# Logic-Board.net
KiCad netlist of a schematic drawn in EAGLE
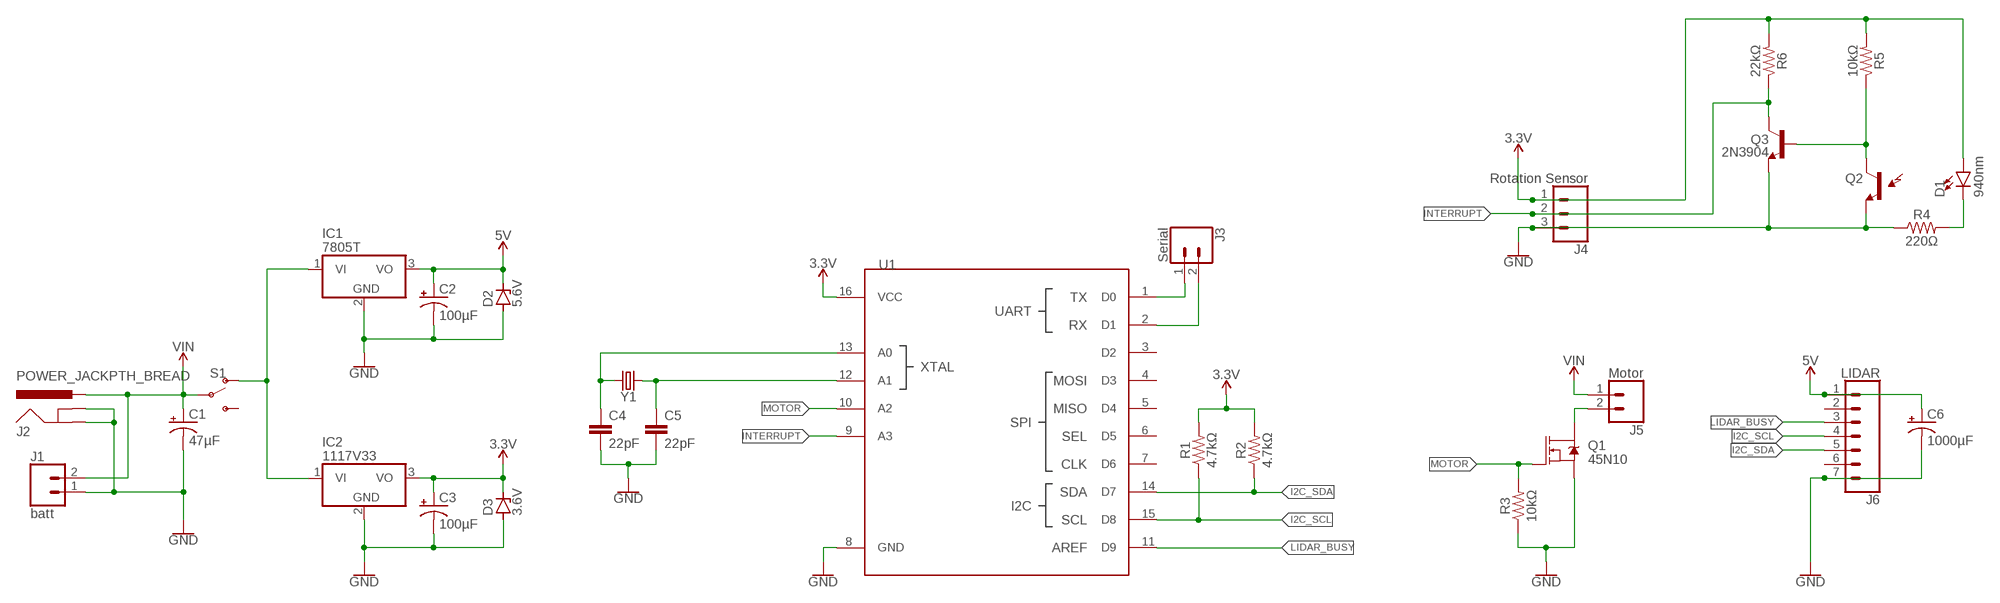
[diagram p0: schematic, sheet 1]

(export (version "E")
  (design (tool "Eeschema 10.0.6"))
  (components
    (comp (ref "C1")
      (value "47µF")
      (footprint "eagle-import:E3,5-10")
      (libsource (lib "eagle-import") (part "CPOL-USE3.5-10"))
    )
    (comp (ref "C2")
      (value "100µF")
      (footprint "eagle-import:E3,5-10")
      (libsource (lib "eagle-import") (part "CPOL-USE3.5-10"))
    )
    (comp (ref "C3")
      (value "100µF")
      (footprint "eagle-import:E3,5-10")
      (libsource (lib "eagle-import") (part "CPOL-USE3.5-10"))
    )
    (comp (ref "C4")
      (value "22pF")
      (footprint "eagle-import:C2.5-3")
      (libsource (lib "eagle-import") (part "C2,5-3"))
    )
    (comp (ref "C5")
      (value "22pF")
      (footprint "eagle-import:C2.5-3")
      (libsource (lib "eagle-import") (part "C2,5-3"))
    )
    (comp (ref "C6")
      (value "1000µF")
      (footprint "eagle-import:E3,5-10")
      (libsource (lib "eagle-import") (part "CPOL-USE3.5-10"))
    )
    (comp (ref "D1")
      (value "940nm")
      (footprint "eagle-import:LED_3MM-NS")
      (libsource (lib "eagle-import") (part "LED-3MM-NO_SILK"))
    )
    (comp (ref "D2")
      (value "5.6V")
      (footprint "eagle-import:DO41Z10")
      (libsource (lib "eagle-import") (part "ZENER-DIODEDO41Z10"))
    )
    (comp (ref "D3")
      (value "3.6V")
      (footprint "eagle-import:DO41Z10")
      (libsource (lib "eagle-import") (part "ZENER-DIODEDO41Z10"))
    )
    (comp (ref "IC1")
      (value "7805T")
      (footprint "eagle-import:TO220H")
      (libsource (lib "eagle-import") (part "78T05"))
    )
    (comp (ref "IC2")
      (value "1117V33")
      (footprint "eagle-import:TO220H")
      (libsource (lib "eagle-import") (part "78T05"))
    )
    (comp (ref "J1")
      (value "batt")
      (footprint "eagle-import:MOLEX-1X2_LOCK")
      (libsource (lib "eagle-import") (part "CONN_02POLAR_LOCK"))
    )
    (comp (ref "J2")
      (value "POWER_JACKPTH_BREAD")
      (footprint "eagle-import:POWER_JACK_PTH_BREAD")
      (libsource (lib "eagle-import") (part "POWER_JACKPTH_BREAD"))
    )
    (comp (ref "J3")
      (value "Serial")
      (footprint "eagle-import:MOLEX-1X2_LOCK")
      (libsource (lib "eagle-import") (part "CONN_02POLAR_LOCK"))
    )
    (comp (ref "J4")
      (value "Rotation Sensor")
      (footprint "eagle-import:MOLEX-1X3")
      (libsource (lib "eagle-import") (part "CONN_03POLAR"))
    )
    (comp (ref "J5")
      (value "Motor")
      (footprint "eagle-import:MOLEX-1X2_LOCK")
      (libsource (lib "eagle-import") (part "CONN_02POLAR_LOCK"))
    )
    (comp (ref "J6")
      (value "LIDAR")
      (footprint "eagle-import:1X07")
      (libsource (lib "eagle-import") (part "CONN_07"))
    )
    (comp (ref "Q1")
      (value "45N10")
      (footprint "eagle-import:TO220V")
      (libsource (lib "eagle-import") (part "MOSFET-NCH-FQP30N06L"))
    )
    (comp (ref "Q2")
      (value "LTR-301")
      (footprint "eagle-import:LTR-301")
      (libsource (lib "eagle-import") (part "LTR-301"))
    )
    (comp (ref "Q3")
      (value "2N3904")
      (footprint "eagle-import:TO-92")
      (libsource (lib "eagle-import") (part "TRANS_NPN-2N3904"))
    )
    (comp (ref "R1")
      (value "4.7kΩ")
      (footprint "eagle-import:AXIAL-0.3-KIT")
      (libsource (lib "eagle-import") (part "1KOHM-HORIZ_KIT-1/4W-1%"))
    )
    (comp (ref "R2")
      (value "4.7kΩ")
      (footprint "eagle-import:AXIAL-0.3-KIT")
      (libsource (lib "eagle-import") (part "1KOHM-HORIZ_KIT-1/4W-1%"))
    )
    (comp (ref "R3")
      (value "10kΩ")
      (footprint "eagle-import:AXIAL-0.3-KIT")
      (libsource (lib "eagle-import") (part "1KOHM-HORIZ_KIT-1/4W-1%"))
    )
    (comp (ref "R4")
      (value "220Ω")
      (footprint "eagle-import:AXIAL-0.3-KIT")
      (libsource (lib "eagle-import") (part "1KOHM-HORIZ_KIT-1/4W-1%"))
    )
    (comp (ref "R5")
      (value "10kΩ")
      (footprint "eagle-import:AXIAL-0.3-KIT")
      (libsource (lib "eagle-import") (part "1KOHM-HORIZ_KIT-1/4W-1%"))
    )
    (comp (ref "R6")
      (value "22kΩ")
      (footprint "eagle-import:AXIAL-0.3-KIT")
      (libsource (lib "eagle-import") (part "1KOHM-HORIZ_KIT-1/4W-1%"))
    )
    (comp (ref "S1")
      (value "SWITCH-SPDT-PTH-11.6X4.0MM")
      (footprint "eagle-import:SWITCH_SPDT_PTH_11.6X4.0MM")
      (libsource (lib "eagle-import") (part "SWITCH-SPDT-PTH-11.6X4.0MM"))
    )
    (comp (ref "U1")
      (value "OSHCHIP")
      (footprint "eagle-import:SOCKET-16")
      (libsource (lib "eagle-import") (part "OSHCHIP"))
    )
    (comp (ref "Y1")
      (value "CRYSTALPTH-3X8")
      (footprint "eagle-import:CRYSTAL-PTH-3X8-CYL")
      (libsource (lib "eagle-import") (part "CRYSTALPTH-3X8"))
    )
  )
  (nets
    (net (code "1") (name "3.3V") (class "Default")
      (node (ref "C3") (pin "+") (pinfunction "+_+") (pintype "passive"))
      (node (ref "D1") (pin "A") (pinfunction "A_A") (pintype "passive"))
      (node (ref "D3") (pin "C") (pinfunction "C_C") (pintype "passive"))
      (node (ref "IC2") (pin "3") (pinfunction "VO_3") (pintype "passive"))
      (node (ref "J4") (pin "1") (pinfunction "1_1") (pintype "passive"))
      (node (ref "R1") (pin "P$2") (pinfunction "2_P$2") (pintype "passive"))
      (node (ref "R2") (pin "P$2") (pinfunction "2_P$2") (pintype "passive"))
      (node (ref "R5") (pin "P$2") (pinfunction "2_P$2") (pintype "passive"))
      (node (ref "R6") (pin "P$2") (pinfunction "2_P$2") (pintype "passive"))
      (node (ref "U1") (pin "16") (pinfunction "VCC_16") (pintype "bidirectional"))
    )
    (net (code "2") (name "5V") (class "Default")
      (node (ref "C2") (pin "+") (pinfunction "+_+") (pintype "passive"))
      (node (ref "C6") (pin "+") (pinfunction "+_+") (pintype "passive"))
      (node (ref "D2") (pin "C") (pinfunction "C_C") (pintype "passive"))
      (node (ref "IC1") (pin "3") (pinfunction "VO_3") (pintype "passive"))
      (node (ref "J6") (pin "1") (pinfunction "1_1") (pintype "passive"))
    )
    (net (code "3") (name "GND") (class "Default")
      (node (ref "C1") (pin "-") (pinfunction "-_-") (pintype "passive"))
      (node (ref "C2") (pin "-") (pinfunction "-_-") (pintype "passive"))
      (node (ref "C3") (pin "-") (pinfunction "-_-") (pintype "passive"))
      (node (ref "C4") (pin "2") (pinfunction "2_2") (pintype "passive"))
      (node (ref "C5") (pin "2") (pinfunction "2_2") (pintype "passive"))
      (node (ref "C6") (pin "-") (pinfunction "-_-") (pintype "passive"))
      (node (ref "D2") (pin "A") (pinfunction "A_A") (pintype "passive"))
      (node (ref "D3") (pin "A") (pinfunction "A_A") (pintype "passive"))
      (node (ref "IC1") (pin "2") (pinfunction "GND_2") (pintype "passive"))
      (node (ref "IC2") (pin "2") (pinfunction "GND_2") (pintype "passive"))
      (node (ref "J1") (pin "1") (pinfunction "1_1") (pintype "passive"))
      (node (ref "J2") (pin "GND") (pinfunction "GND_GND") (pintype "bidirectional"))
      (node (ref "J2") (pin "GNDBREAK") (pinfunction "GNDBREAK_GNDBREAK") (pintype "bidirectional"))
      (node (ref "J4") (pin "3") (pinfunction "3_3") (pintype "passive"))
      (node (ref "J6") (pin "7") (pinfunction "7_7") (pintype "passive"))
      (node (ref "Q1") (pin "3") (pinfunction "S_3") (pintype "bidirectional"))
      (node (ref "Q2") (pin "E") (pinfunction "E1_E") (pintype "passive"))
      (node (ref "Q3") (pin "1") (pinfunction "E_1") (pintype "passive"))
      (node (ref "R3") (pin "P$1") (pinfunction "1_P$1") (pintype "passive"))
      (node (ref "R4") (pin "P$1") (pinfunction "1_P$1") (pintype "passive"))
      (node (ref "U1") (pin "8") (pinfunction "GND_8") (pintype "bidirectional"))
    )
    (net (code "4") (name "I2C_SCL") (class "Default")
      (node (ref "J6") (pin "4") (pinfunction "4_4") (pintype "passive"))
      (node (ref "R1") (pin "P$1") (pinfunction "1_P$1") (pintype "passive"))
      (node (ref "U1") (pin "15") (pinfunction "D8_15") (pintype "bidirectional"))
    )
    (net (code "5") (name "I2C_SDA") (class "Default")
      (node (ref "J6") (pin "5") (pinfunction "5_5") (pintype "passive"))
      (node (ref "R2") (pin "P$1") (pinfunction "1_P$1") (pintype "passive"))
      (node (ref "U1") (pin "14") (pinfunction "D7_14") (pintype "bidirectional"))
    )
    (net (code "6") (name "INTERRUPT") (class "Default")
      (node (ref "J4") (pin "2") (pinfunction "2_2") (pintype "passive"))
      (node (ref "Q3") (pin "3") (pinfunction "C_3") (pintype "passive"))
      (node (ref "R6") (pin "P$1") (pinfunction "1_P$1") (pintype "passive"))
      (node (ref "U1") (pin "9") (pinfunction "A3_9") (pintype "bidirectional"))
    )
    (net (code "7") (name "LIDAR_BUSY") (class "Default")
      (node (ref "J6") (pin "3") (pinfunction "3_3") (pintype "passive"))
      (node (ref "U1") (pin "11") (pinfunction "D9_11") (pintype "bidirectional"))
    )
    (net (code "8") (name "MOTOR") (class "Default")
      (node (ref "Q1") (pin "1") (pinfunction "G_1") (pintype "bidirectional"))
      (node (ref "R3") (pin "P$2") (pinfunction "2_P$2") (pintype "passive"))
      (node (ref "U1") (pin "10") (pinfunction "A2_10") (pintype "bidirectional"))
    )
    (net (code "9") (name "Net-(D1-C)") (class "Default")
      (node (ref "D1") (pin "K") (pinfunction "C_K") (pintype "passive"))
      (node (ref "R4") (pin "P$2") (pinfunction "2_P$2") (pintype "passive"))
    )
    (net (code "10") (name "Net-(IC1-VI)") (class "Default")
      (node (ref "IC1") (pin "1") (pinfunction "VI_1") (pintype "input"))
      (node (ref "IC2") (pin "1") (pinfunction "VI_1") (pintype "input"))
      (node (ref "S1") (pin "1") (pinfunction "O_1") (pintype "passive"))
    )
    (net (code "11") (name "Net-(Q1-D)") (class "Default")
      (node (ref "J5") (pin "2") (pinfunction "2_2") (pintype "passive"))
      (node (ref "Q1") (pin "2") (pinfunction "D_2") (pintype "bidirectional"))
    )
    (net (code "12") (name "Net-(Q2-C1)") (class "Default")
      (node (ref "Q2") (pin "C") (pinfunction "C1_C") (pintype "passive"))
      (node (ref "Q3") (pin "2") (pinfunction "B_2") (pintype "passive"))
      (node (ref "R5") (pin "P$1") (pinfunction "1_P$1") (pintype "passive"))
    )
    (net (code "13") (name "Net-(U1-A0)") (class "Default")
      (node (ref "C4") (pin "1") (pinfunction "1_1") (pintype "passive"))
      (node (ref "U1") (pin "13") (pinfunction "A0_13") (pintype "bidirectional"))
      (node (ref "Y1") (pin "2") (pinfunction "2_2") (pintype "passive"))
    )
    (net (code "14") (name "Net-(U1-A1)") (class "Default")
      (node (ref "C5") (pin "1") (pinfunction "1_1") (pintype "passive"))
      (node (ref "U1") (pin "12") (pinfunction "A1_12") (pintype "bidirectional"))
      (node (ref "Y1") (pin "1") (pinfunction "1_1") (pintype "passive"))
    )
    (net (code "15") (name "Net-(U1-D0)") (class "Default")
      (node (ref "J3") (pin "1") (pinfunction "1_1") (pintype "passive"))
      (node (ref "U1") (pin "1") (pinfunction "D0_1") (pintype "bidirectional"))
    )
    (net (code "16") (name "Net-(U1-D1)") (class "Default")
      (node (ref "J3") (pin "2") (pinfunction "2_2") (pintype "passive"))
      (node (ref "U1") (pin "2") (pinfunction "D1_2") (pintype "bidirectional"))
    )
    (net (code "17") (name "VIN") (class "Default")
      (node (ref "C1") (pin "+") (pinfunction "+_+") (pintype "passive"))
      (node (ref "J1") (pin "2") (pinfunction "2_2") (pintype "passive"))
      (node (ref "J2") (pin "PWR") (pinfunction "PWR_PWR") (pintype "bidirectional"))
      (node (ref "J5") (pin "1") (pinfunction "1_1") (pintype "passive"))
      (node (ref "S1") (pin "2") (pinfunction "P_2") (pintype "passive"))
    )
    (net (code "18") (name "unconnected-(J6-Pad2)") (class "Default")
      (node (ref "J6") (pin "2") (pinfunction "2_2") (pintype "passive"))
    )
    (net (code "19") (name "unconnected-(J6-Pad6)") (class "Default")
      (node (ref "J6") (pin "6") (pinfunction "6_6") (pintype "passive"))
    )
    (net (code "20") (name "unconnected-(S1-S-Pad3)") (class "Default")
      (node (ref "S1") (pin "3") (pinfunction "S_3") (pintype "passive"))
    )
    (net (code "21") (name "unconnected-(U1-D2-Pad3)") (class "Default")
      (node (ref "U1") (pin "3") (pinfunction "D2_3") (pintype "bidirectional"))
    )
    (net (code "22") (name "unconnected-(U1-D3-Pad4)") (class "Default")
      (node (ref "U1") (pin "4") (pinfunction "D3_4") (pintype "bidirectional"))
    )
    (net (code "23") (name "unconnected-(U1-D4-Pad5)") (class "Default")
      (node (ref "U1") (pin "5") (pinfunction "D4_5") (pintype "bidirectional"))
    )
    (net (code "24") (name "unconnected-(U1-D5-Pad6)") (class "Default")
      (node (ref "U1") (pin "6") (pinfunction "D5_6") (pintype "bidirectional"))
    )
    (net (code "25") (name "unconnected-(U1-D6-Pad7)") (class "Default")
      (node (ref "U1") (pin "7") (pinfunction "D6_7") (pintype "bidirectional"))
    )
  )
)
